# BMS_Adapter_rev5.net
KiCad netlist of a schematic drawn in EAGLE
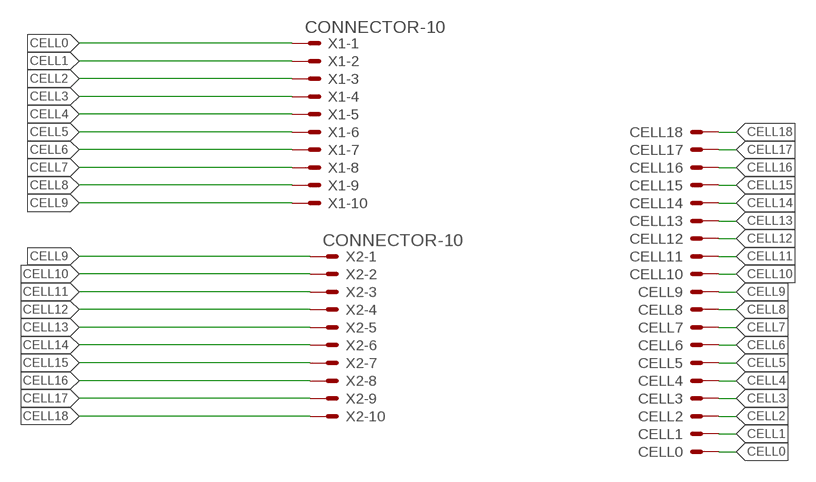
[diagram p0: schematic, sheet 1]

(export (version "E")
  (design (tool "Eeschema 10.0.6"))
  (components
    (comp (ref "CELL0")
      (value "BATTERY_SPRING")
      (footprint "eagle-import:KEYSTONE5203")
      (libsource (lib "eagle-import") (part "BATTERY_SPRING"))
    )
    (comp (ref "CELL1")
      (value "BATTERY_SPRING")
      (footprint "eagle-import:KEYSTONE5203")
      (libsource (lib "eagle-import") (part "BATTERY_SPRING"))
    )
    (comp (ref "CELL2")
      (value "BATTERY_SPRING")
      (footprint "eagle-import:KEYSTONE5203")
      (libsource (lib "eagle-import") (part "BATTERY_SPRING"))
    )
    (comp (ref "CELL3")
      (value "BATTERY_SPRING")
      (footprint "eagle-import:KEYSTONE5203")
      (libsource (lib "eagle-import") (part "BATTERY_SPRING"))
    )
    (comp (ref "CELL4")
      (value "BATTERY_SPRING")
      (footprint "eagle-import:KEYSTONE5203")
      (libsource (lib "eagle-import") (part "BATTERY_SPRING"))
    )
    (comp (ref "CELL5")
      (value "BATTERY_SPRING")
      (footprint "eagle-import:KEYSTONE5203")
      (libsource (lib "eagle-import") (part "BATTERY_SPRING"))
    )
    (comp (ref "CELL6")
      (value "BATTERY_SPRING")
      (footprint "eagle-import:KEYSTONE5203")
      (libsource (lib "eagle-import") (part "BATTERY_SPRING"))
    )
    (comp (ref "CELL7")
      (value "BATTERY_SPRING")
      (footprint "eagle-import:KEYSTONE5203")
      (libsource (lib "eagle-import") (part "BATTERY_SPRING"))
    )
    (comp (ref "CELL8")
      (value "BATTERY_SPRING")
      (footprint "eagle-import:KEYSTONE5203")
      (libsource (lib "eagle-import") (part "BATTERY_SPRING"))
    )
    (comp (ref "CELL9")
      (value "BATTERY_SPRING")
      (footprint "eagle-import:KEYSTONE5203")
      (libsource (lib "eagle-import") (part "BATTERY_SPRING"))
    )
    (comp (ref "CELL10")
      (value "BATTERY_SPRING")
      (footprint "eagle-import:KEYSTONE5203")
      (libsource (lib "eagle-import") (part "BATTERY_SPRING"))
    )
    (comp (ref "CELL11")
      (value "BATTERY_SPRING")
      (footprint "eagle-import:KEYSTONE5203")
      (libsource (lib "eagle-import") (part "BATTERY_SPRING"))
    )
    (comp (ref "CELL12")
      (value "BATTERY_SPRING")
      (footprint "eagle-import:KEYSTONE5203")
      (libsource (lib "eagle-import") (part "BATTERY_SPRING"))
    )
    (comp (ref "CELL13")
      (value "BATTERY_SPRING")
      (footprint "eagle-import:KEYSTONE5203")
      (libsource (lib "eagle-import") (part "BATTERY_SPRING"))
    )
    (comp (ref "CELL14")
      (value "BATTERY_SPRING")
      (footprint "eagle-import:KEYSTONE5203")
      (libsource (lib "eagle-import") (part "BATTERY_SPRING"))
    )
    (comp (ref "CELL15")
      (value "BATTERY_SPRING")
      (footprint "eagle-import:KEYSTONE5203")
      (libsource (lib "eagle-import") (part "BATTERY_SPRING"))
    )
    (comp (ref "CELL16")
      (value "BATTERY_SPRING")
      (footprint "eagle-import:KEYSTONE5203")
      (libsource (lib "eagle-import") (part "BATTERY_SPRING"))
    )
    (comp (ref "CELL17")
      (value "BATTERY_SPRING")
      (footprint "eagle-import:KEYSTONE5203")
      (libsource (lib "eagle-import") (part "BATTERY_SPRING"))
    )
    (comp (ref "CELL18")
      (value "BATTERY_SPRING")
      (footprint "eagle-import:KEYSTONE5203")
      (libsource (lib "eagle-import") (part "BATTERY_SPRING"))
    )
    (comp (ref "X1")
      (value "CONNECTOR-10")
      (footprint "eagle-import:MINIFIT_5566-10")
      (libsource (lib "eagle-import") (part "CONNECTOR-10"))
    )
    (comp (ref "X2")
      (value "CONNECTOR-10")
      (footprint "eagle-import:MINIFIT_5566-10")
      (libsource (lib "eagle-import") (part "CONNECTOR-10"))
    )
  )
  (nets
    (net (code "1") (name "CELL0") (class "Default")
      (node (ref "CELL0") (pin "P$1") (pinfunction "S_P$1") (pintype "passive"))
      (node (ref "X1") (pin "1") (pinfunction "S_1") (pintype "passive"))
    )
    (net (code "2") (name "CELL1") (class "Default")
      (node (ref "CELL1") (pin "P$1") (pinfunction "S_P$1") (pintype "passive"))
      (node (ref "X1") (pin "2") (pinfunction "S_2") (pintype "passive"))
    )
    (net (code "3") (name "CELL2") (class "Default")
      (node (ref "CELL2") (pin "P$1") (pinfunction "S_P$1") (pintype "passive"))
      (node (ref "X1") (pin "3") (pinfunction "S_3") (pintype "passive"))
    )
    (net (code "4") (name "CELL3") (class "Default")
      (node (ref "CELL3") (pin "P$1") (pinfunction "S_P$1") (pintype "passive"))
      (node (ref "X1") (pin "4") (pinfunction "S_4") (pintype "passive"))
    )
    (net (code "5") (name "CELL4") (class "Default")
      (node (ref "CELL4") (pin "P$1") (pinfunction "S_P$1") (pintype "passive"))
      (node (ref "X1") (pin "5") (pinfunction "S_5") (pintype "passive"))
    )
    (net (code "6") (name "CELL5") (class "Default")
      (node (ref "CELL5") (pin "P$1") (pinfunction "S_P$1") (pintype "passive"))
      (node (ref "X1") (pin "6") (pinfunction "S_6") (pintype "passive"))
    )
    (net (code "7") (name "CELL6") (class "Default")
      (node (ref "CELL6") (pin "P$1") (pinfunction "S_P$1") (pintype "passive"))
      (node (ref "X1") (pin "7") (pinfunction "S_7") (pintype "passive"))
    )
    (net (code "8") (name "CELL7") (class "Default")
      (node (ref "CELL7") (pin "P$1") (pinfunction "S_P$1") (pintype "passive"))
      (node (ref "X1") (pin "8") (pinfunction "S_8") (pintype "passive"))
    )
    (net (code "9") (name "CELL8") (class "Default")
      (node (ref "CELL8") (pin "P$1") (pinfunction "S_P$1") (pintype "passive"))
      (node (ref "X1") (pin "9") (pinfunction "S_9") (pintype "passive"))
    )
    (net (code "10") (name "CELL9") (class "Default")
      (node (ref "CELL9") (pin "P$1") (pinfunction "S_P$1") (pintype "passive"))
      (node (ref "X1") (pin "10") (pinfunction "S_10") (pintype "passive"))
      (node (ref "X2") (pin "1") (pinfunction "S_1") (pintype "passive"))
    )
    (net (code "11") (name "CELL10") (class "Default")
      (node (ref "CELL10") (pin "P$1") (pinfunction "S_P$1") (pintype "passive"))
      (node (ref "X2") (pin "2") (pinfunction "S_2") (pintype "passive"))
    )
    (net (code "12") (name "CELL11") (class "Default")
      (node (ref "CELL11") (pin "P$1") (pinfunction "S_P$1") (pintype "passive"))
      (node (ref "X2") (pin "3") (pinfunction "S_3") (pintype "passive"))
    )
    (net (code "13") (name "CELL12") (class "Default")
      (node (ref "CELL12") (pin "P$1") (pinfunction "S_P$1") (pintype "passive"))
      (node (ref "X2") (pin "4") (pinfunction "S_4") (pintype "passive"))
    )
    (net (code "14") (name "CELL13") (class "Default")
      (node (ref "CELL13") (pin "P$1") (pinfunction "S_P$1") (pintype "passive"))
      (node (ref "X2") (pin "5") (pinfunction "S_5") (pintype "passive"))
    )
    (net (code "15") (name "CELL14") (class "Default")
      (node (ref "CELL14") (pin "P$1") (pinfunction "S_P$1") (pintype "passive"))
      (node (ref "X2") (pin "6") (pinfunction "S_6") (pintype "passive"))
    )
    (net (code "16") (name "CELL15") (class "Default")
      (node (ref "CELL15") (pin "P$1") (pinfunction "S_P$1") (pintype "passive"))
      (node (ref "X2") (pin "7") (pinfunction "S_7") (pintype "passive"))
    )
    (net (code "17") (name "CELL16") (class "Default")
      (node (ref "CELL16") (pin "P$1") (pinfunction "S_P$1") (pintype "passive"))
      (node (ref "X2") (pin "8") (pinfunction "S_8") (pintype "passive"))
    )
    (net (code "18") (name "CELL17") (class "Default")
      (node (ref "CELL17") (pin "P$1") (pinfunction "S_P$1") (pintype "passive"))
      (node (ref "X2") (pin "9") (pinfunction "S_9") (pintype "passive"))
    )
    (net (code "19") (name "CELL18") (class "Default")
      (node (ref "CELL18") (pin "P$1") (pinfunction "S_P$1") (pintype "passive"))
      (node (ref "X2") (pin "10") (pinfunction "S_10") (pintype "passive"))
    )
  )
)
